# other.net
KiCad netlist of a schematic drawn in Altium Designer
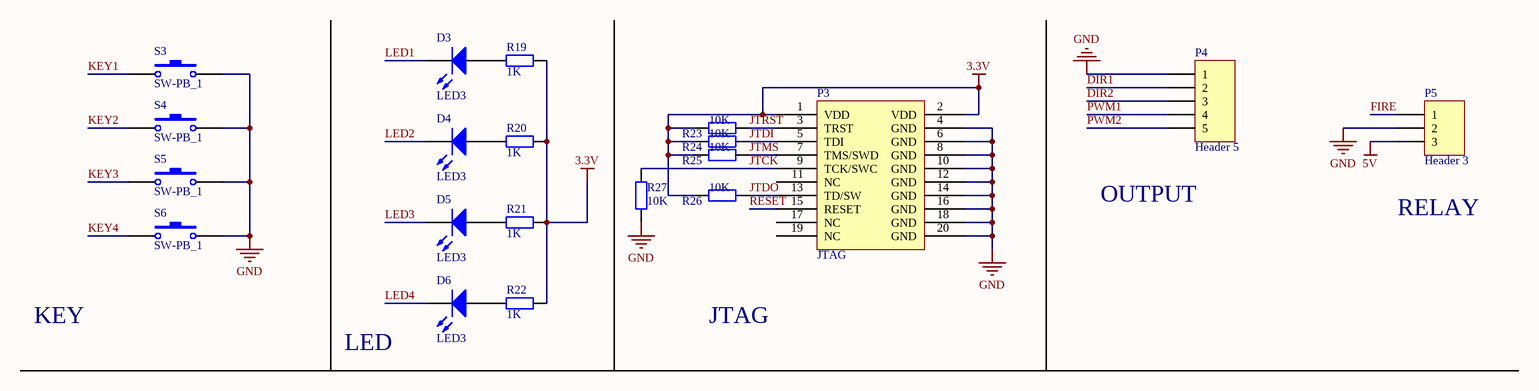
[diagram p0: other.SchDoc]

(export (version "E")
  (design (tool "Eeschema 10.0.6"))
  (components
    (comp (ref "D3")
      (value "LED3")
      (footprint "0603-1")
      (description "Typical BLUE SiC LED")
      (fields (field (name "PUBLISHER") "Altium Limited"))
      (libsource (lib "Miscellaneous Devices") (part "LED3"))
    )
    (comp (ref "D4")
      (value "LED3")
      (footprint "0603-1")
      (description "Typical BLUE SiC LED")
      (fields (field (name "PUBLISHER") "Altium Limited"))
      (libsource (lib "Miscellaneous Devices") (part "LED3"))
    )
    (comp (ref "D5")
      (value "LED3")
      (footprint "0603-1")
      (description "Typical BLUE SiC LED")
      (fields (field (name "PUBLISHER") "Altium Limited"))
      (libsource (lib "Miscellaneous Devices") (part "LED3"))
    )
    (comp (ref "D6")
      (value "LED3")
      (footprint "0603-1")
      (description "Typical BLUE SiC LED")
      (fields (field (name "PUBLISHER") "Altium Limited"))
      (libsource (lib "Miscellaneous Devices") (part "LED3"))
    )
    (comp (ref "P3") (value "JTAG") (footprint "JTAG") (libsource (lib "mcu_board") (part "JTAG")))
    (comp (ref "P4")
      (value "Header 5")
      (footprint "HDR1X5")
      (description "Header, 5-Pin")
      (fields (field (name "PUBLISHER") "Altium Limited"))
      (libsource (lib "Miscellaneous Connectors") (part "Header 5"))
    )
    (comp (ref "P5")
      (value "Header 3")
      (footprint "HDR1X3")
      (description "Header, 3-Pin")
      (fields (field (name "PUBLISHER") "Altium Limited"))
      (libsource (lib "Miscellaneous Connectors") (part "Header 3"))
    )
    (comp (ref "R19")
      (value "1K")
      (footprint "R-0603")
      (description "Resistor")
      (fields (field (name "Comment") "Res2") (field (name "PUBLISHER") "Altium Limited"))
      (libsource (lib "Miscellaneous Devices") (part "Res2"))
    )
    (comp (ref "R20")
      (value "1K")
      (footprint "R-0603")
      (description "Resistor")
      (fields (field (name "Comment") "Res2") (field (name "PUBLISHER") "Altium Limited"))
      (libsource (lib "Miscellaneous Devices") (part "Res2"))
    )
    (comp (ref "R21")
      (value "1K")
      (footprint "R-0603")
      (description "Resistor")
      (fields (field (name "Comment") "Res2") (field (name "PUBLISHER") "Altium Limited"))
      (libsource (lib "Miscellaneous Devices") (part "Res2"))
    )
    (comp (ref "R22")
      (value "1K")
      (footprint "R-0603")
      (description "Resistor")
      (fields (field (name "Comment") "Res2") (field (name "PUBLISHER") "Altium Limited"))
      (libsource (lib "Miscellaneous Devices") (part "Res2"))
    )
    (comp (ref "R23")
      (value "10K")
      (footprint "R-0603")
      (description "Resistor")
      (fields (field (name "Comment") "Res2") (field (name "PUBLISHER") "Altium Limited"))
      (libsource (lib "Miscellaneous Devices") (part "Res2"))
    )
    (comp (ref "R24")
      (value "10K")
      (footprint "R-0603")
      (description "Resistor")
      (fields (field (name "Comment") "Res2") (field (name "PUBLISHER") "Altium Limited"))
      (libsource (lib "Miscellaneous Devices") (part "Res2"))
    )
    (comp (ref "R25")
      (value "10K")
      (footprint "R-0603")
      (description "Resistor")
      (fields (field (name "Comment") "Res2") (field (name "PUBLISHER") "Altium Limited"))
      (libsource (lib "Miscellaneous Devices") (part "Res2"))
    )
    (comp (ref "R26")
      (value "10K")
      (footprint "R-0603")
      (description "Resistor")
      (fields (field (name "Comment") "Res2") (field (name "PUBLISHER") "Altium Limited"))
      (libsource (lib "Miscellaneous Devices") (part "Res2"))
    )
    (comp (ref "R27")
      (value "10K")
      (footprint "R-0603")
      (description "Resistor")
      (fields (field (name "Comment") "Res2") (field (name "PUBLISHER") "Altium Limited"))
      (libsource (lib "") (part "Res2_1"))
    )
    (comp (ref "S3")
      (value "SW-PB_1")
      (footprint "SW-2-6*3")
      (description "Switch")
      (fields (field (name "PUBLISHER") "Altium Limited"))
      (libsource (lib "mcu_board") (part "SW-PB_1"))
    )
    (comp (ref "S4")
      (value "SW-PB_1")
      (footprint "SW-2-6*3")
      (description "Switch")
      (fields (field (name "PUBLISHER") "Altium Limited"))
      (libsource (lib "mcu_board") (part "SW-PB_1"))
    )
    (comp (ref "S5")
      (value "SW-PB_1")
      (footprint "SW-2-6*3")
      (description "Switch")
      (fields (field (name "PUBLISHER") "Altium Limited"))
      (libsource (lib "mcu_board") (part "SW-PB_1"))
    )
    (comp (ref "S6")
      (value "SW-PB_1")
      (footprint "SW-2-6*3")
      (description "Switch")
      (fields (field (name "PUBLISHER") "Altium Limited"))
      (libsource (lib "mcu_board") (part "SW-PB_1"))
    )
  )
  (nets
    (net (code "1") (name "/DIR1") (class "Default")
      (node (ref "P4") (pin "2") (pinfunction "2_2") (pintype "passive"))
    )
    (net (code "2") (name "/DIR2") (class "Default")
      (node (ref "P4") (pin "3") (pinfunction "3_3") (pintype "passive"))
    )
    (net (code "3") (name "/FIRE") (class "Default")
      (node (ref "P5") (pin "1") (pinfunction "1_1") (pintype "passive"))
    )
    (net (code "4") (name "/JTCK") (class "Default")
      (node (ref "P3") (pin "9") (pinfunction "TCK/SWC_9") (pintype "passive"))
      (node (ref "R27") (pin "1") (pinfunction "1_1") (pintype "passive"))
    )
    (net (code "5") (name "/JTDI") (class "Default")
      (node (ref "P3") (pin "5") (pinfunction "TDI_5") (pintype "passive"))
      (node (ref "R24") (pin "1") (pinfunction "1_1") (pintype "passive"))
    )
    (net (code "6") (name "/JTDO") (class "Default")
      (node (ref "P3") (pin "13") (pinfunction "TD/SW_13") (pintype "passive"))
      (node (ref "R26") (pin "1") (pinfunction "1_1") (pintype "passive"))
    )
    (net (code "7") (name "/JTMS") (class "Default")
      (node (ref "P3") (pin "7") (pinfunction "TMS/SWD_7") (pintype "passive"))
      (node (ref "R25") (pin "1") (pinfunction "1_1") (pintype "passive"))
    )
    (net (code "8") (name "/JTRST") (class "Default")
      (node (ref "P3") (pin "3") (pinfunction "TRST_3") (pintype "passive"))
      (node (ref "R23") (pin "1") (pinfunction "1_1") (pintype "passive"))
    )
    (net (code "9") (name "/KEY1") (class "Default")
      (node (ref "S3") (pin "1") (pinfunction "1_1") (pintype "passive"))
    )
    (net (code "10") (name "/KEY2") (class "Default")
      (node (ref "S4") (pin "1") (pinfunction "1_1") (pintype "passive"))
    )
    (net (code "11") (name "/KEY3") (class "Default")
      (node (ref "S5") (pin "1") (pinfunction "1_1") (pintype "passive"))
    )
    (net (code "12") (name "/KEY4") (class "Default")
      (node (ref "S6") (pin "1") (pinfunction "1_1") (pintype "passive"))
    )
    (net (code "13") (name "/LED1") (class "Default")
      (node (ref "D3") (pin "2") (pinfunction "K_2") (pintype "passive"))
    )
    (net (code "14") (name "/LED2") (class "Default")
      (node (ref "D4") (pin "2") (pinfunction "K_2") (pintype "passive"))
    )
    (net (code "15") (name "/LED3") (class "Default")
      (node (ref "D5") (pin "2") (pinfunction "K_2") (pintype "passive"))
    )
    (net (code "16") (name "/LED4") (class "Default")
      (node (ref "D6") (pin "2") (pinfunction "K_2") (pintype "passive"))
    )
    (net (code "17") (name "/PWM1") (class "Default")
      (node (ref "P4") (pin "4") (pinfunction "4_4") (pintype "passive"))
    )
    (net (code "18") (name "/PWM2") (class "Default")
      (node (ref "P4") (pin "5") (pinfunction "5_5") (pintype "passive"))
    )
    (net (code "19") (name "/RESET") (class "Default")
      (node (ref "P3") (pin "15") (pinfunction "RESET_15") (pintype "passive"))
    )
    (net (code "20") (name "3.3V") (class "Default")
      (node (ref "P3") (pin "1") (pinfunction "VDD_1") (pintype "passive"))
      (node (ref "P3") (pin "2") (pinfunction "VDD_2") (pintype "passive"))
      (node (ref "R19") (pin "1") (pinfunction "1_1") (pintype "passive"))
      (node (ref "R20") (pin "1") (pinfunction "1_1") (pintype "passive"))
      (node (ref "R21") (pin "1") (pinfunction "1_1") (pintype "passive"))
      (node (ref "R22") (pin "1") (pinfunction "1_1") (pintype "passive"))
      (node (ref "R23") (pin "2") (pinfunction "2_2") (pintype "passive"))
      (node (ref "R24") (pin "2") (pinfunction "2_2") (pintype "passive"))
      (node (ref "R25") (pin "2") (pinfunction "2_2") (pintype "passive"))
      (node (ref "R26") (pin "2") (pinfunction "2_2") (pintype "passive"))
    )
    (net (code "21") (name "5V") (class "Default")
      (node (ref "P5") (pin "3") (pinfunction "3_3") (pintype "passive"))
    )
    (net (code "22") (name "GND") (class "Default")
      (node (ref "P3") (pin "10") (pinfunction "GND_10") (pintype "passive"))
      (node (ref "P3") (pin "12") (pinfunction "GND_12") (pintype "passive"))
      (node (ref "P3") (pin "14") (pinfunction "GND_14") (pintype "passive"))
      (node (ref "P3") (pin "16") (pinfunction "GND_16") (pintype "passive"))
      (node (ref "P3") (pin "18") (pinfunction "GND_18") (pintype "passive"))
      (node (ref "P3") (pin "20") (pinfunction "GND_20") (pintype "passive"))
      (node (ref "P3") (pin "4") (pinfunction "GND_4") (pintype "passive"))
      (node (ref "P3") (pin "6") (pinfunction "GND_6") (pintype "passive"))
      (node (ref "P3") (pin "8") (pinfunction "GND_8") (pintype "passive"))
      (node (ref "P4") (pin "1") (pinfunction "1_1") (pintype "passive"))
      (node (ref "P5") (pin "2") (pinfunction "2_2") (pintype "passive"))
      (node (ref "R27") (pin "2") (pinfunction "2_2") (pintype "passive"))
      (node (ref "S3") (pin "2") (pinfunction "2_2") (pintype "passive"))
      (node (ref "S4") (pin "2") (pinfunction "2_2") (pintype "passive"))
      (node (ref "S5") (pin "2") (pinfunction "2_2") (pintype "passive"))
      (node (ref "S6") (pin "2") (pinfunction "2_2") (pintype "passive"))
    )
    (net (code "23") (name "Net-(D3-A)") (class "Default")
      (node (ref "D3") (pin "1") (pinfunction "A_1") (pintype "passive"))
      (node (ref "R19") (pin "2") (pinfunction "2_2") (pintype "passive"))
    )
    (net (code "24") (name "Net-(D4-A)") (class "Default")
      (node (ref "D4") (pin "1") (pinfunction "A_1") (pintype "passive"))
      (node (ref "R20") (pin "2") (pinfunction "2_2") (pintype "passive"))
    )
    (net (code "25") (name "Net-(D5-A)") (class "Default")
      (node (ref "D5") (pin "1") (pinfunction "A_1") (pintype "passive"))
      (node (ref "R21") (pin "2") (pinfunction "2_2") (pintype "passive"))
    )
    (net (code "26") (name "Net-(D6-A)") (class "Default")
      (node (ref "D6") (pin "1") (pinfunction "A_1") (pintype "passive"))
      (node (ref "R22") (pin "2") (pinfunction "2_2") (pintype "passive"))
    )
    (net (code "27") (name "unconnected-(P3-NC-Pad11)") (class "Default")
      (node (ref "P3") (pin "11") (pinfunction "NC_11") (pintype "passive"))
    )
    (net (code "28") (name "unconnected-(P3-NC-Pad17)") (class "Default")
      (node (ref "P3") (pin "17") (pinfunction "NC_17") (pintype "passive"))
    )
    (net (code "29") (name "unconnected-(P3-NC-Pad19)") (class "Default")
      (node (ref "P3") (pin "19") (pinfunction "NC_19") (pintype "passive"))
    )
  )
)
